# bai_3.net
KiCad netlist of a schematic drawn in Altium Designer
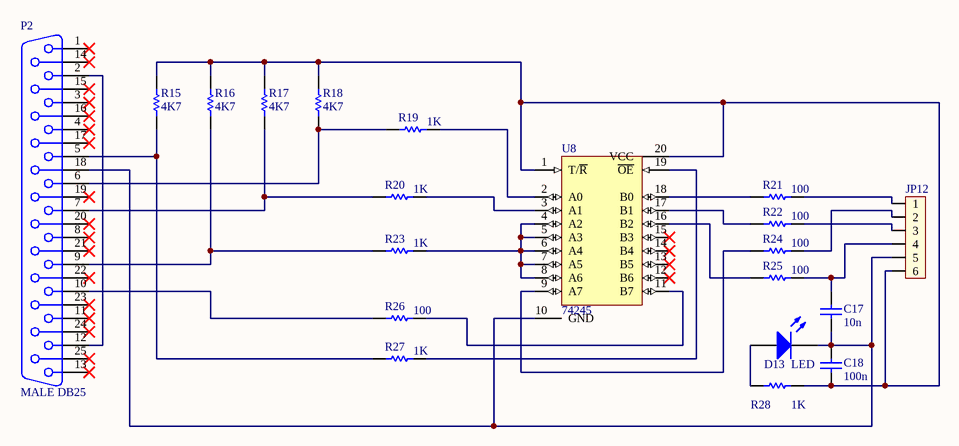
[diagram p0: bai 3.SchDoc]

(export (version "E")
  (design (tool "Eeschema 10.0.6"))
  (components
    (comp (ref "C17")
      (value "10n")
      (footprint "RAD-0.3")
      (description "Capacitor")
      (fields (field (name "Comment") "Cap") (field (name "PUBLISHER") "Altium Limited"))
      (libsource (lib "Miscellaneous Devices") (part "Cap"))
    )
    (comp (ref "C18")
      (value "100n")
      (footprint "RAD-0.3")
      (description "Capacitor")
      (fields (field (name "Comment") "Cap") (field (name "PUBLISHER") "Altium Limited"))
      (libsource (lib "Miscellaneous Devices") (part "Cap"))
    )
    (comp (ref "D13")
      (value "LED")
      (footprint "LED-1")
      (description "Typical RED GaAs LED")
      (fields (field (name "PUBLISHER") "Altium Limited"))
      (libsource (lib "Miscellaneous Devices") (part "LED1"))
    )
    (comp (ref "JP12") (value "JP6 PIN") (footprint "JP6") (libsource (lib "syhaunguyen") (part "JP6")))
    (comp (ref "P2")
      (value "MALE DB25")
      (footprint "DSB 25-F")
      (description "LPT 25")
      (fields (field (name "PUBLISHER") "Altium Limited"))
      (libsource (lib "syhaunguyen") (part "DSB 25"))
    )
    (comp (ref "R15")
      (value "4K7")
      (footprint "R1/4W")
      (description "Resistor")
      (fields
        (field (name "MANUFACTURER") "Generic Components")
        (field (name "Comment") "Res1")
        (field (name "PUBLISHER") "Altium Hobart Technology Centre")
      )
      (libsource (lib "syhaunguyen") (part "Res1_1"))
    )
    (comp (ref "R16")
      (value "4K7")
      (footprint "R1/4W")
      (description "Resistor")
      (fields
        (field (name "MANUFACTURER") "Generic Components")
        (field (name "Comment") "Res1")
        (field (name "PUBLISHER") "Altium Hobart Technology Centre")
      )
      (libsource (lib "syhaunguyen") (part "Res1_1"))
    )
    (comp (ref "R17")
      (value "4K7")
      (footprint "R1/4W")
      (description "Resistor")
      (fields
        (field (name "MANUFACTURER") "Generic Components")
        (field (name "Comment") "Res1")
        (field (name "PUBLISHER") "Altium Hobart Technology Centre")
      )
      (libsource (lib "syhaunguyen") (part "Res1_1"))
    )
    (comp (ref "R18")
      (value "4K7")
      (footprint "R1/4W")
      (description "Resistor")
      (fields
        (field (name "MANUFACTURER") "Generic Components")
        (field (name "Comment") "Res1")
        (field (name "PUBLISHER") "Altium Hobart Technology Centre")
      )
      (libsource (lib "syhaunguyen") (part "Res1_1"))
    )
    (comp (ref "R19")
      (value "1K")
      (footprint "R1/4W")
      (description "Resistor")
      (fields
        (field (name "MANUFACTURER") "Generic Components")
        (field (name "Comment") "Res1")
        (field (name "PUBLISHER") "Altium Hobart Technology Centre")
      )
      (libsource (lib "syhaunguyen") (part "Res1_1"))
    )
    (comp (ref "R20")
      (value "1K")
      (footprint "R1/4W")
      (description "Resistor")
      (fields
        (field (name "MANUFACTURER") "Generic Components")
        (field (name "Comment") "Res1")
        (field (name "PUBLISHER") "Altium Hobart Technology Centre")
      )
      (libsource (lib "syhaunguyen") (part "Res1_1"))
    )
    (comp (ref "R21")
      (value "100")
      (footprint "R1/4W1")
      (description "Resistor")
      (fields
        (field (name "MANUFACTURER") "Generic Components")
        (field (name "Comment") "Res1")
        (field (name "PUBLISHER") "Altium Hobart Technology Centre")
      )
      (libsource (lib "syhaunguyen") (part "Res1_5"))
    )
    (comp (ref "R22")
      (value "100")
      (footprint "R1/4W1")
      (description "Resistor")
      (fields
        (field (name "MANUFACTURER") "Generic Components")
        (field (name "Comment") "Res1")
        (field (name "PUBLISHER") "Altium Hobart Technology Centre")
      )
      (libsource (lib "syhaunguyen") (part "Res1_5"))
    )
    (comp (ref "R23")
      (value "1K")
      (footprint "R1/4W")
      (description "Resistor")
      (fields
        (field (name "MANUFACTURER") "Generic Components")
        (field (name "Comment") "Res1")
        (field (name "PUBLISHER") "Altium Hobart Technology Centre")
      )
      (libsource (lib "syhaunguyen") (part "Res1_1"))
    )
    (comp (ref "R24")
      (value "100")
      (footprint "R1/4W1")
      (description "Resistor")
      (fields
        (field (name "MANUFACTURER") "Generic Components")
        (field (name "Comment") "Res1")
        (field (name "PUBLISHER") "Altium Hobart Technology Centre")
      )
      (libsource (lib "syhaunguyen") (part "Res1_5"))
    )
    (comp (ref "R25")
      (value "100")
      (footprint "R1/4W1")
      (description "Resistor")
      (fields
        (field (name "MANUFACTURER") "Generic Components")
        (field (name "Comment") "Res1")
        (field (name "PUBLISHER") "Altium Hobart Technology Centre")
      )
      (libsource (lib "syhaunguyen") (part "Res1_5"))
    )
    (comp (ref "R26")
      (value "100")
      (footprint "R1/4W1")
      (description "Resistor")
      (fields
        (field (name "MANUFACTURER") "Generic Components")
        (field (name "Comment") "Res1")
        (field (name "PUBLISHER") "Altium Hobart Technology Centre")
      )
      (libsource (lib "syhaunguyen") (part "Res1_5"))
    )
    (comp (ref "R27")
      (value "1K")
      (footprint "R1/4W")
      (description "Resistor")
      (fields
        (field (name "MANUFACTURER") "Generic Components")
        (field (name "Comment") "Res1")
        (field (name "PUBLISHER") "Altium Hobart Technology Centre")
      )
      (libsource (lib "syhaunguyen") (part "Res1_1"))
    )
    (comp (ref "R28")
      (value "1K")
      (footprint "R1/4W")
      (description "Resistor")
      (fields
        (field (name "MANUFACTURER") "Generic Components")
        (field (name "Comment") "Res1")
        (field (name "PUBLISHER") "Altium Hobart Technology Centre")
      )
      (libsource (lib "syhaunguyen") (part "Res1_1"))
    )
    (comp (ref "U8")
      (value "74245")
      (footprint "DIP20/W0.3")
      (description "Octal bus tranceiver; 3-state")
      (fields (field (name "COPYRIGHT BY") "VanDungEvn@gmail.com"))
      (libsource (lib "syhaunguyen") (part "74245"))
    )
  )
  (nets
    (net (code "1") (name "GND") (class "Default")
      (node (ref "C17") (pin "1") (pinfunction "1_1") (pintype "passive"))
      (node (ref "C18") (pin "2") (pinfunction "2_2") (pintype "passive"))
      (node (ref "D13") (pin "2") (pinfunction "K_2") (pintype "passive"))
      (node (ref "JP12") (pin "5") (pinfunction "5_5") (pintype "passive"))
      (node (ref "P2") (pin "18") (pinfunction "18_18") (pintype "passive"))
      (node (ref "U8") (pin "10") (pinfunction "GND_10") (pintype "power_in"))
    )
    (net (code "2") (name "Net-(C17-Pad2)") (class "Default")
      (node (ref "C17") (pin "2") (pinfunction "2_2") (pintype "passive"))
      (node (ref "JP12") (pin "4") (pinfunction "4_4") (pintype "passive"))
      (node (ref "R25") (pin "1") (pinfunction "1_1") (pintype "passive"))
    )
    (net (code "3") (name "Net-(D13-A)") (class "Default")
      (node (ref "D13") (pin "1") (pinfunction "A_1") (pintype "passive"))
      (node (ref "R28") (pin "2") (pinfunction "2_2") (pintype "passive"))
    )
    (net (code "4") (name "Net-(JP12-Pad1)") (class "Default")
      (node (ref "JP12") (pin "1") (pinfunction "1_1") (pintype "passive"))
      (node (ref "R21") (pin "1") (pinfunction "1_1") (pintype "passive"))
    )
    (net (code "5") (name "Net-(JP12-Pad2)") (class "Default")
      (node (ref "JP12") (pin "2") (pinfunction "2_2") (pintype "passive"))
      (node (ref "R24") (pin "1") (pinfunction "1_1") (pintype "passive"))
    )
    (net (code "6") (name "Net-(JP12-Pad3)") (class "Default")
      (node (ref "JP12") (pin "3") (pinfunction "3_3") (pintype "passive"))
      (node (ref "R22") (pin "1") (pinfunction "1_1") (pintype "passive"))
    )
    (net (code "7") (name "Net-(P2-Pad5)") (class "Default")
      (node (ref "P2") (pin "5") (pinfunction "5_5") (pintype "passive"))
      (node (ref "R15") (pin "1") (pinfunction "1_1") (pintype "passive"))
      (node (ref "R27") (pin "2") (pinfunction "2_2") (pintype "passive"))
    )
    (net (code "8") (name "Net-(P2-Pad6)") (class "Default")
      (node (ref "P2") (pin "6") (pinfunction "6_6") (pintype "passive"))
      (node (ref "R18") (pin "1") (pinfunction "1_1") (pintype "passive"))
      (node (ref "R19") (pin "2") (pinfunction "2_2") (pintype "passive"))
    )
    (net (code "9") (name "Net-(P2-Pad7)") (class "Default")
      (node (ref "P2") (pin "7") (pinfunction "7_7") (pintype "passive"))
      (node (ref "R17") (pin "1") (pinfunction "1_1") (pintype "passive"))
      (node (ref "R20") (pin "2") (pinfunction "2_2") (pintype "passive"))
    )
    (net (code "10") (name "Net-(P2-Pad9)") (class "Default")
      (node (ref "P2") (pin "9") (pinfunction "9_9") (pintype "passive"))
      (node (ref "R16") (pin "1") (pinfunction "1_1") (pintype "passive"))
      (node (ref "R23") (pin "2") (pinfunction "2_2") (pintype "passive"))
    )
    (net (code "11") (name "Net-(P2-Pad10)") (class "Default")
      (node (ref "P2") (pin "10") (pinfunction "10_10") (pintype "passive"))
      (node (ref "R26") (pin "2") (pinfunction "2_2") (pintype "passive"))
    )
    (net (code "12") (name "Net-(P2-Pad12)") (class "Default")
      (node (ref "P2") (pin "12") (pinfunction "12_12") (pintype "passive"))
      (node (ref "P2") (pin "2") (pinfunction "2_2") (pintype "passive"))
    )
    (net (code "13") (name "Net-(U8-A0)") (class "Default")
      (node (ref "R19") (pin "1") (pinfunction "1_1") (pintype "passive"))
      (node (ref "U8") (pin "2") (pinfunction "A0_2") (pintype "bidirectional"))
    )
    (net (code "14") (name "Net-(U8-A1)") (class "Default")
      (node (ref "R20") (pin "1") (pinfunction "1_1") (pintype "passive"))
      (node (ref "U8") (pin "3") (pinfunction "A1_3") (pintype "bidirectional"))
    )
    (net (code "15") (name "Net-(U8-A2)") (class "Default")
      (node (ref "R23") (pin "1") (pinfunction "1_1") (pintype "passive"))
      (node (ref "U8") (pin "4") (pinfunction "A2_4") (pintype "bidirectional"))
      (node (ref "U8") (pin "5") (pinfunction "A3_5") (pintype "bidirectional"))
      (node (ref "U8") (pin "6") (pinfunction "A4_6") (pintype "bidirectional"))
      (node (ref "U8") (pin "7") (pinfunction "A5_7") (pintype "bidirectional"))
      (node (ref "U8") (pin "8") (pinfunction "A6_8") (pintype "bidirectional"))
    )
    (net (code "16") (name "Net-(U8-A7)") (class "Default")
      (node (ref "R24") (pin "2") (pinfunction "2_2") (pintype "passive"))
      (node (ref "U8") (pin "9") (pinfunction "A7_9") (pintype "bidirectional"))
    )
    (net (code "17") (name "Net-(U8-B0)") (class "Default")
      (node (ref "R21") (pin "2") (pinfunction "2_2") (pintype "passive"))
      (node (ref "U8") (pin "18") (pinfunction "B0_18") (pintype "bidirectional"))
    )
    (net (code "18") (name "Net-(U8-B1)") (class "Default")
      (node (ref "R22") (pin "2") (pinfunction "2_2") (pintype "passive"))
      (node (ref "U8") (pin "17") (pinfunction "B1_17") (pintype "bidirectional"))
    )
    (net (code "19") (name "Net-(U8-B2)") (class "Default")
      (node (ref "R25") (pin "2") (pinfunction "2_2") (pintype "passive"))
      (node (ref "U8") (pin "16") (pinfunction "B2_16") (pintype "bidirectional"))
    )
    (net (code "20") (name "Net-(U8-B7)") (class "Default")
      (node (ref "R26") (pin "1") (pinfunction "1_1") (pintype "passive"))
      (node (ref "U8") (pin "11") (pinfunction "B7_11") (pintype "bidirectional"))
    )
    (net (code "21") (name "Net-(U8-~{OE})") (class "Default")
      (node (ref "R27") (pin "1") (pinfunction "1_1") (pintype "passive"))
      (node (ref "U8") (pin "19") (pinfunction "~{OE}_19") (pintype "input"))
    )
    (net (code "22") (name "VCC") (class "Default")
      (node (ref "C18") (pin "1") (pinfunction "1_1") (pintype "passive"))
      (node (ref "JP12") (pin "6") (pinfunction "6_6") (pintype "passive"))
      (node (ref "R15") (pin "2") (pinfunction "2_2") (pintype "passive"))
      (node (ref "R16") (pin "2") (pinfunction "2_2") (pintype "passive"))
      (node (ref "R17") (pin "2") (pinfunction "2_2") (pintype "passive"))
      (node (ref "R18") (pin "2") (pinfunction "2_2") (pintype "passive"))
      (node (ref "R28") (pin "1") (pinfunction "1_1") (pintype "passive"))
      (node (ref "U8") (pin "1") (pinfunction "T/~{R}_1") (pintype "input"))
      (node (ref "U8") (pin "20") (pinfunction "VCC_20") (pintype "power_in"))
    )
    (net (code "23") (name "unconnected-(P2-MH1-Pad26)") (class "Default")
      (node (ref "P2") (pin "26") (pinfunction "MH1_26") (pintype "passive"))
    )
    (net (code "24") (name "unconnected-(P2-MH2-Pad27)") (class "Default")
      (node (ref "P2") (pin "27") (pinfunction "MH2_27") (pintype "passive"))
    )
    (net (code "25") (name "unconnected-(P2-Pad1)") (class "Default")
      (node (ref "P2") (pin "1") (pinfunction "1_1") (pintype "passive+no_connect"))
    )
    (net (code "26") (name "unconnected-(P2-Pad3)") (class "Default")
      (node (ref "P2") (pin "3") (pinfunction "3_3") (pintype "passive+no_connect"))
    )
    (net (code "27") (name "unconnected-(P2-Pad4)") (class "Default")
      (node (ref "P2") (pin "4") (pinfunction "4_4") (pintype "passive+no_connect"))
    )
    (net (code "28") (name "unconnected-(P2-Pad8)") (class "Default")
      (node (ref "P2") (pin "8") (pinfunction "8_8") (pintype "passive+no_connect"))
    )
    (net (code "29") (name "unconnected-(P2-Pad11)") (class "Default")
      (node (ref "P2") (pin "11") (pinfunction "11_11") (pintype "passive+no_connect"))
    )
    (net (code "30") (name "unconnected-(P2-Pad13)") (class "Default")
      (node (ref "P2") (pin "13") (pinfunction "13_13") (pintype "passive+no_connect"))
    )
    (net (code "31") (name "unconnected-(P2-Pad14)") (class "Default")
      (node (ref "P2") (pin "14") (pinfunction "14_14") (pintype "passive+no_connect"))
    )
    (net (code "32") (name "unconnected-(P2-Pad15)") (class "Default")
      (node (ref "P2") (pin "15") (pinfunction "15_15") (pintype "passive+no_connect"))
    )
    (net (code "33") (name "unconnected-(P2-Pad16)") (class "Default")
      (node (ref "P2") (pin "16") (pinfunction "16_16") (pintype "passive+no_connect"))
    )
    (net (code "34") (name "unconnected-(P2-Pad17)") (class "Default")
      (node (ref "P2") (pin "17") (pinfunction "17_17") (pintype "passive+no_connect"))
    )
    (net (code "35") (name "unconnected-(P2-Pad19)") (class "Default")
      (node (ref "P2") (pin "19") (pinfunction "19_19") (pintype "passive+no_connect"))
    )
    (net (code "36") (name "unconnected-(P2-Pad20)") (class "Default")
      (node (ref "P2") (pin "20") (pinfunction "20_20") (pintype "passive+no_connect"))
    )
    (net (code "37") (name "unconnected-(P2-Pad21)") (class "Default")
      (node (ref "P2") (pin "21") (pinfunction "21_21") (pintype "passive+no_connect"))
    )
    (net (code "38") (name "unconnected-(P2-Pad22)") (class "Default")
      (node (ref "P2") (pin "22") (pinfunction "22_22") (pintype "passive+no_connect"))
    )
    (net (code "39") (name "unconnected-(P2-Pad23)") (class "Default")
      (node (ref "P2") (pin "23") (pinfunction "23_23") (pintype "passive+no_connect"))
    )
    (net (code "40") (name "unconnected-(P2-Pad24)") (class "Default")
      (node (ref "P2") (pin "24") (pinfunction "24_24") (pintype "passive+no_connect"))
    )
    (net (code "41") (name "unconnected-(P2-Pad25)") (class "Default")
      (node (ref "P2") (pin "25") (pinfunction "25_25") (pintype "passive+no_connect"))
    )
    (net (code "42") (name "unconnected-(U8-B3-Pad15)") (class "Default")
      (node (ref "U8") (pin "15") (pinfunction "B3_15") (pintype "bidirectional+no_connect"))
    )
    (net (code "43") (name "unconnected-(U8-B4-Pad14)") (class "Default")
      (node (ref "U8") (pin "14") (pinfunction "B4_14") (pintype "bidirectional+no_connect"))
    )
    (net (code "44") (name "unconnected-(U8-B5-Pad13)") (class "Default")
      (node (ref "U8") (pin "13") (pinfunction "B5_13") (pintype "bidirectional+no_connect"))
    )
    (net (code "45") (name "unconnected-(U8-B6-Pad12)") (class "Default")
      (node (ref "U8") (pin "12") (pinfunction "B6_12") (pintype "bidirectional+no_connect"))
    )
  )
)
